# Connectors.net
KiCad netlist of a schematic drawn in Altium Designer
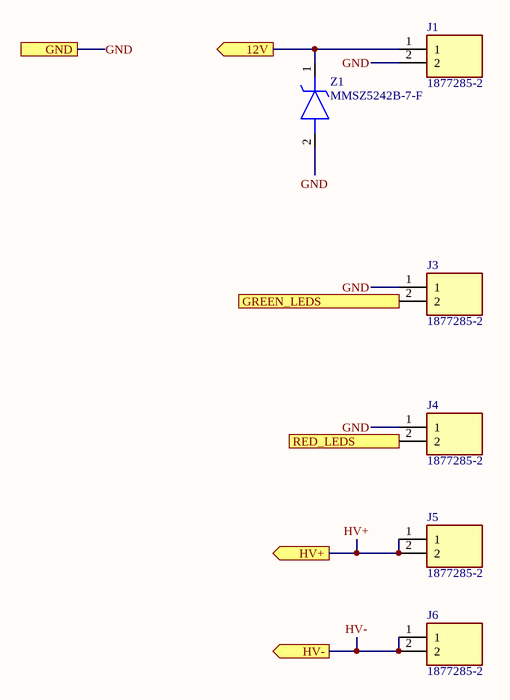
[diagram p0: Connectors.SchDoc]

(export (version "E")
  (design (tool "Eeschema 10.0.6"))
  (components
    (comp (ref "J1")
      (value "1877285-2")
      (footprint "18772852")
      (description "Connector")
      (fields (field (name "MOUSER PART NUMBER") "571-1877285-2"))
      (libsource (lib "SamacSys") (part "1877285-2"))
    )
    (comp (ref "J3")
      (value "1877285-2")
      (footprint "18772852")
      (description "Connector")
      (fields (field (name "MOUSER PART NUMBER") "571-1877285-2"))
      (libsource (lib "SamacSys") (part "1877285-2"))
    )
    (comp (ref "J4")
      (value "1877285-2")
      (footprint "18772852")
      (description "Connector")
      (fields (field (name "MOUSER PART NUMBER") "571-1877285-2"))
      (libsource (lib "SamacSys") (part "1877285-2"))
    )
    (comp (ref "J5")
      (value "1877285-2")
      (footprint "18772852")
      (description "Connector")
      (fields (field (name "MOUSER PART NUMBER") "571-1877285-2"))
      (libsource (lib "SamacSys") (part "1877285-2"))
    )
    (comp (ref "J6")
      (value "1877285-2")
      (footprint "18772852")
      (description "Connector")
      (fields (field (name "MOUSER PART NUMBER") "571-1877285-2"))
      (libsource (lib "SamacSys") (part "1877285-2"))
    )
    (comp (ref "Z1")
      (value "MMSZ5242B-7-F")
      (footprint "SamacSys:SOD3716X145N")
      (description "Zener Diode")
      (fields (field (name "MOUSER PART NUMBER") "621-MMSZ5242B-F"))
      (libsource (lib "SamacSys") (part "MMSZ5242B-7-F"))
    )
  )
  (nets
    (net (code "1") (name "/12V") (class "Default")
      (node (ref "J1") (pin "1") (pinfunction "1_1") (pintype "passive"))
      (node (ref "Z1") (pin "1") (pinfunction "K_1") (pintype "passive"))
    )
    (net (code "2") (name "/GND") (class "Default")
      (node (ref "J1") (pin "2") (pinfunction "2_2") (pintype "passive"))
      (node (ref "J3") (pin "1") (pinfunction "1_1") (pintype "passive"))
      (node (ref "J4") (pin "1") (pinfunction "1_1") (pintype "passive"))
      (node (ref "Z1") (pin "2") (pinfunction "A_2") (pintype "passive"))
    )
    (net (code "3") (name "/GREEN_LEDS") (class "Default")
      (node (ref "J3") (pin "2") (pinfunction "2_2") (pintype "passive"))
    )
    (net (code "4") (name "/HV+") (class "Default")
      (node (ref "J5") (pin "1") (pinfunction "1_1") (pintype "passive"))
      (node (ref "J5") (pin "2") (pinfunction "2_2") (pintype "passive"))
    )
    (net (code "5") (name "/HV-") (class "Default")
      (node (ref "J6") (pin "1") (pinfunction "1_1") (pintype "passive"))
      (node (ref "J6") (pin "2") (pinfunction "2_2") (pintype "passive"))
    )
    (net (code "6") (name "/RED_LEDS") (class "Default")
      (node (ref "J4") (pin "2") (pinfunction "2_2") (pintype "passive"))
    )
  )
)
